# LED.net
KiCad netlist of a schematic drawn in Altium Designer
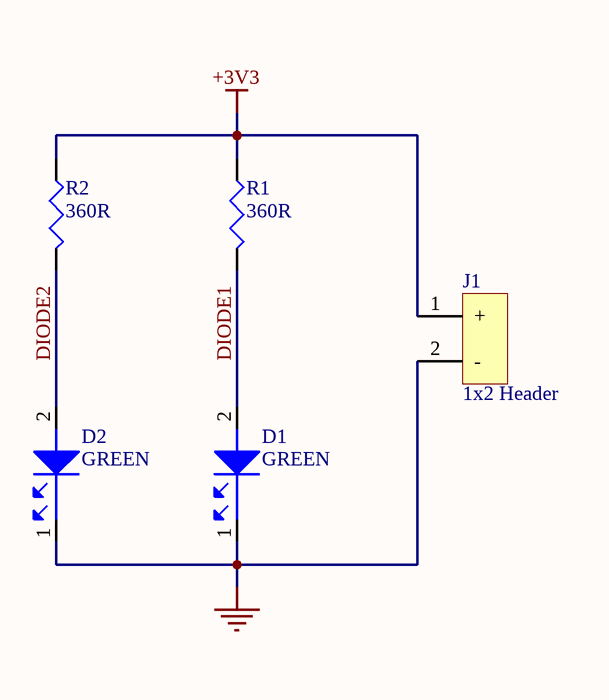
[diagram p0: LED.SchDoc]

(export (version "E")
  (design (tool "Eeschema 10.0.6"))
  (components
    (comp (ref "D1")
      (value "GREEN")
      (footprint "LED0603G")
      (description "LNJ337W83RA; ESS II Series Yellow-Green LED; 572 nm 1608(0603); Rectangle Lens")
      (fields
        (field (name "MANUFACTURER") "Panasonic SSG")
        (field (name "MANUFACTURER PART NUMBER") "LNJ337W83RA")
      )
      (libsource (lib "LED_Schlib") (part "LNJ337W83RA"))
    )
    (comp (ref "D2")
      (value "GREEN")
      (footprint "LED0603G")
      (description "LNJ337W83RA; ESS II Series Yellow-Green LED; 572 nm 1608(0603); Rectangle Lens")
      (fields
        (field (name "MANUFACTURER") "Panasonic SSG")
        (field (name "MANUFACTURER PART NUMBER") "LNJ337W83RA")
      )
      (libsource (lib "LED_Schlib") (part "LNJ337W83RA"))
    )
    (comp (ref "J1")
      (value "1x2 Header")
      (footprint "HEADER_1X2")
      (description "KK 254 Wire-to-Board Header, Vertical, with Friction Lock, 2 Circuits, Gold (Au) Plating")
      (fields (field (name "MANUFACTURER") "Molex") (field (name "MANUFACTURER PART NUMBER") "22-29-2021"))
      (libsource (lib "LED_Schlib") (part "22-29-2021"))
    )
    (comp (ref "R1")
      (value "360R")
      (footprint "R0805")
      (description "Res Thick Film 0805 360 Ohm 1% 1/8W ±100ppm/°C Molded SMD SMD Paper T/R")
      (fields
        (field (name "MANUFACTURER") "Vishay")
        (field (name "MANUFACTURER PART NUMBER") "CRCW0805360RFKEA")
      )
      (libsource (lib "LED_Schlib") (part "CRCW0805360RFKEA"))
    )
    (comp (ref "R2")
      (value "360R")
      (footprint "R0805")
      (description "Res Thick Film 0805 360 Ohm 1% 1/8W ±100ppm/°C Molded SMD SMD Paper T/R")
      (fields
        (field (name "MANUFACTURER") "Vishay")
        (field (name "MANUFACTURER PART NUMBER") "CRCW0805360RFKEA")
      )
      (libsource (lib "LED_Schlib") (part "CRCW0805360RFKEA"))
    )
  )
  (nets
    (net (code "1") (name "+3V3") (class "Default")
      (node (ref "J1") (pin "1") (pinfunction "+_1") (pintype "passive"))
      (node (ref "R1") (pin "1") (pinfunction "1_1") (pintype "passive"))
      (node (ref "R2") (pin "1") (pinfunction "1_1") (pintype "passive"))
    )
    (net (code "2") (name "/DIODE1") (class "Default")
      (node (ref "D1") (pin "2") (pinfunction "2_2") (pintype "passive"))
      (node (ref "R1") (pin "2") (pinfunction "2_2") (pintype "passive"))
    )
    (net (code "3") (name "/DIODE2") (class "Default")
      (node (ref "D2") (pin "2") (pinfunction "2_2") (pintype "passive"))
      (node (ref "R2") (pin "2") (pinfunction "2_2") (pintype "passive"))
    )
    (net (code "4") (name "GND") (class "Default")
      (node (ref "D1") (pin "1") (pinfunction "1_1") (pintype "passive"))
      (node (ref "D2") (pin "1") (pinfunction "1_1") (pintype "passive"))
      (node (ref "J1") (pin "2") (pinfunction "-_2") (pintype "passive"))
    )
  )
)
